# Power_Switch.net
KiCad netlist of a schematic drawn in EasyEDA Pro
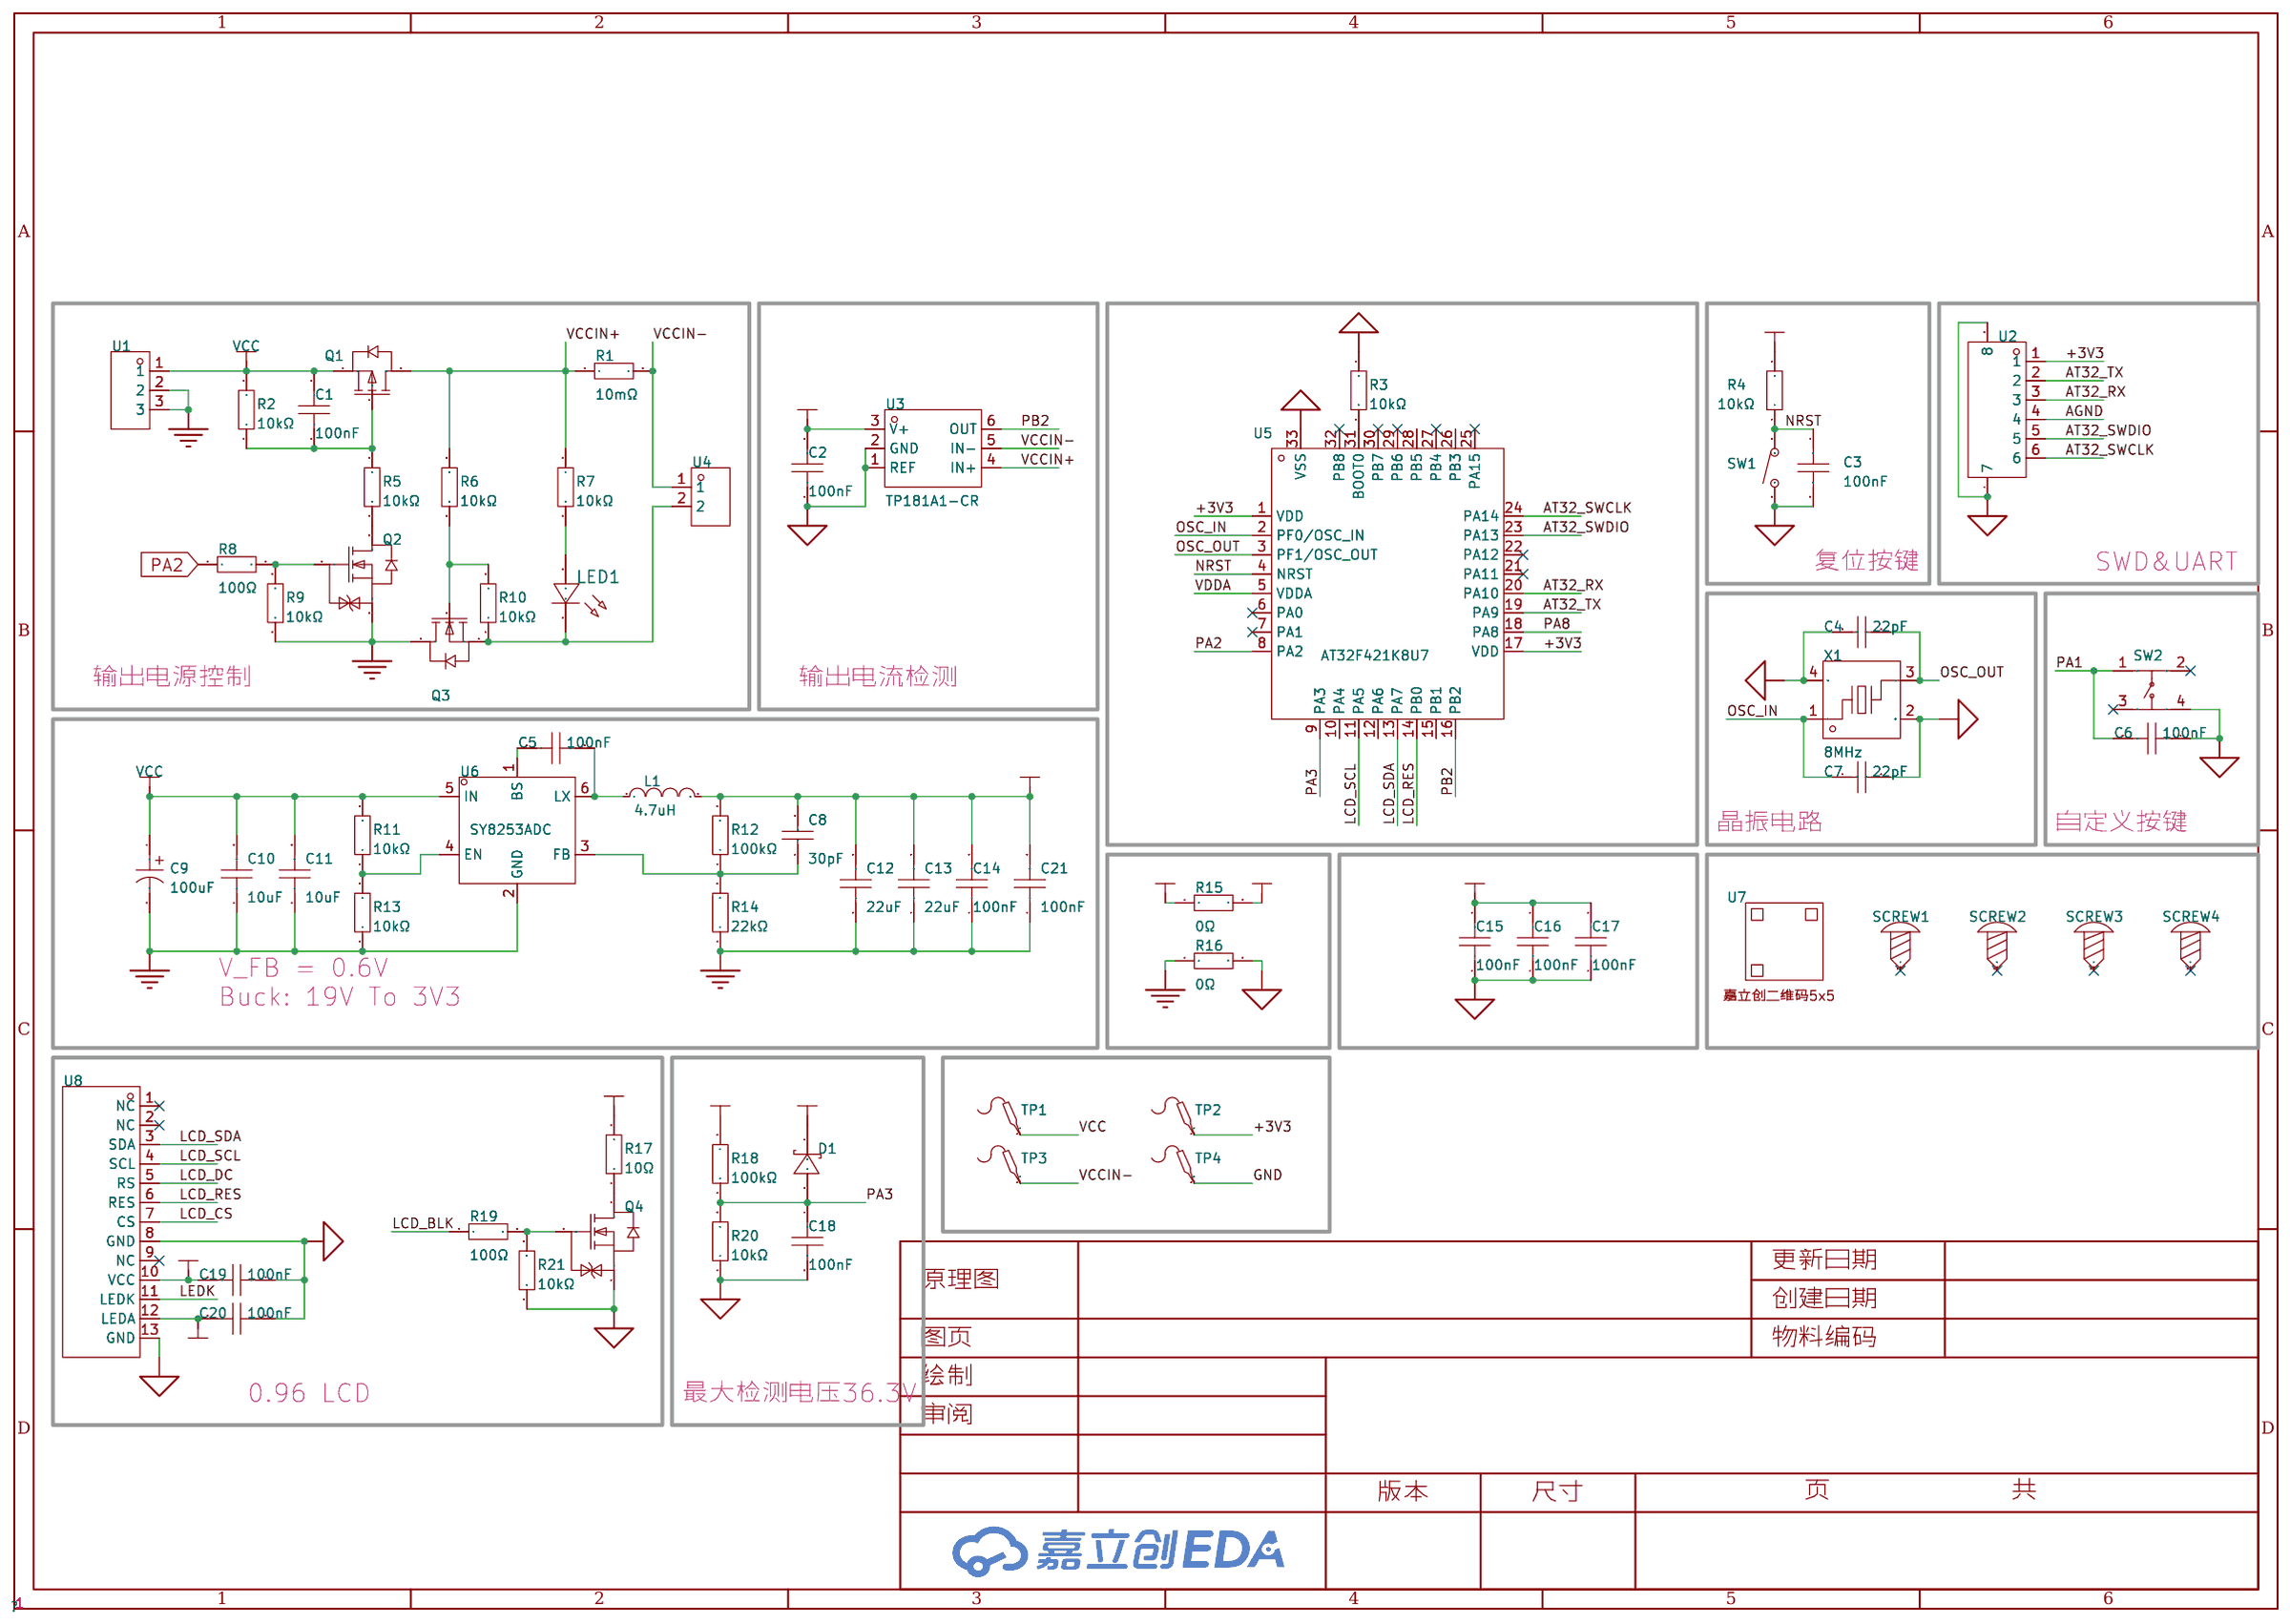
[diagram p0: schematic sheet]

(export (version "E")
  (design (tool "Eeschema 10.0.6"))
  (components
    (comp (ref "C1")
      (value "100nF")
      (footprint "easyedapro:C0402")
      (description "容值:100nF;精度:±10%;额定电压:50V;材质(温度系数):X7R;")
      (fields
        (field (name "Manufacturer Part") "CL05B104KB54PNC")
        (field (name "Manufacturer") "SAMSUNG(三星)")
      )
      (libsource (lib "easyedapro") (part "CL05B104KB54PNC"))
    )
    (comp (ref "C2")
      (value "100nF")
      (footprint "easyedapro:C0402")
      (description "容值:100nF;精度:±10%;额定电压:50V;材质(温度系数):X7R;")
      (fields
        (field (name "Manufacturer Part") "CL05B104KB54PNC")
        (field (name "Manufacturer") "SAMSUNG(三星)")
      )
      (libsource (lib "easyedapro") (part "CL05B104KB54PNC"))
    )
    (comp (ref "C3")
      (value "100nF")
      (footprint "easyedapro:C0402")
      (description "容值:100nF;精度:±10%;额定电压:50V;材质(温度系数):X7R;")
      (fields
        (field (name "Manufacturer Part") "CL05B104KB54PNC")
        (field (name "Manufacturer") "SAMSUNG(三星)")
      )
      (libsource (lib "easyedapro") (part "CL05B104KB54PNC"))
    )
    (comp (ref "C4")
      (value "22pF")
      (footprint "easyedapro:C0402")
      (description "容值:22pF;精度:±5%;额定电压:50V;材质(温度系数):C0G;")
      (fields (field (name "Manufacturer Part") "0402CG220J500NT") (field (name "Manufacturer") "FH(风华)"))
      (libsource (lib "easyedapro") (part "0402CG220J500NT"))
    )
    (comp (ref "C5")
      (value "100nF")
      (footprint "easyedapro:C0402")
      (description "容值:100nF;精度:±10%;额定电压:50V;材质(温度系数):X7R;")
      (fields
        (field (name "Manufacturer Part") "CL05B104KB54PNC")
        (field (name "Manufacturer") "SAMSUNG(三星)")
      )
      (libsource (lib "easyedapro") (part "CL05B104KB54PNC"))
    )
    (comp (ref "C6")
      (value "100nF")
      (footprint "easyedapro:C0402")
      (description "容值:100nF;精度:±10%;额定电压:50V;材质(温度系数):X7R;")
      (fields
        (field (name "Manufacturer Part") "CL05B104KB54PNC")
        (field (name "Manufacturer") "SAMSUNG(三星)")
      )
      (libsource (lib "easyedapro") (part "CL05B104KB54PNC"))
    )
    (comp (ref "C7")
      (value "22pF")
      (footprint "easyedapro:C0402")
      (description "容值:22pF;精度:±5%;额定电压:50V;材质(温度系数):C0G;")
      (fields (field (name "Manufacturer Part") "0402CG220J500NT") (field (name "Manufacturer") "FH(风华)"))
      (libsource (lib "easyedapro") (part "0402CG220J500NT"))
    )
    (comp (ref "C8")
      (value "30pF")
      (footprint "easyedapro:C0402")
      (description "容值:30pF;精度:±5%;额定电压:50V;材质(温度系数):NP0;")
      (fields
        (field (name "Manufacturer Part") "CC0402JRNPO9BN300")
        (field (name "Manufacturer") "YAGEO(国巨)")
      )
      (libsource (lib "easyedapro") (part "CC0402JRNPO9BN300"))
    )
    (comp (ref "C9")
      (value "100uF")
      (footprint "easyedapro:CAP-SMD_BD6.3-L6.6-W6.6-LS7.4-FD")
      (description "容值:100uF;精度:±20%;额定电压:35V;纹波电流:87mA@120kHz;等效串联电阻:-;")
      (fields
        (field (name "Manufacturer Part") "RVT100UF35V67RV0034")
        (field (name "Manufacturer") "KNSCHA(科尼盛)")
      )
      (libsource (lib "easyedapro") (part "RVT100UF35V67RV0034"))
    )
    (comp (ref "C10")
      (value "10uF")
      (footprint "easyedapro:C0805")
      (description "容值:10uF;精度:±10%;额定电压:25V;材质(温度系数):X5R;")
      (fields
        (field (name "Manufacturer Part") "CL21A106KAYNNNE")
        (field (name "Manufacturer") "SAMSUNG(三星)")
      )
      (libsource (lib "easyedapro") (part "CL21A106KAYNNNE"))
    )
    (comp (ref "C11")
      (value "10uF")
      (footprint "easyedapro:C0805")
      (description "容值:10uF;精度:±10%;额定电压:25V;材质(温度系数):X5R;")
      (fields
        (field (name "Manufacturer Part") "CL21A106KAYNNNE")
        (field (name "Manufacturer") "SAMSUNG(三星)")
      )
      (libsource (lib "easyedapro") (part "CL21A106KAYNNNE"))
    )
    (comp (ref "C12")
      (value "22uF")
      (footprint "easyedapro:C0603")
      (description "容值:22uF;精度:±20%;额定电压:6.3V;材质(温度系数):X5R;")
      (fields
        (field (name "Manufacturer Part") "CL10A226MQ8NRNC")
        (field (name "Manufacturer") "SAMSUNG(三星)")
      )
      (libsource (lib "easyedapro") (part "CL10A226MQ8NRNC"))
    )
    (comp (ref "C13")
      (value "22uF")
      (footprint "easyedapro:C0603")
      (description "容值:22uF;精度:±20%;额定电压:6.3V;材质(温度系数):X5R;")
      (fields
        (field (name "Manufacturer Part") "CL10A226MQ8NRNC")
        (field (name "Manufacturer") "SAMSUNG(三星)")
      )
      (libsource (lib "easyedapro") (part "CL10A226MQ8NRNC"))
    )
    (comp (ref "C14")
      (value "100nF")
      (footprint "easyedapro:C0402")
      (description "容值:100nF;精度:±10%;额定电压:50V;材质(温度系数):X7R;")
      (fields
        (field (name "Manufacturer Part") "CL05B104KB54PNC")
        (field (name "Manufacturer") "SAMSUNG(三星)")
      )
      (libsource (lib "easyedapro") (part "CL05B104KB54PNC"))
    )
    (comp (ref "C15")
      (value "100nF")
      (footprint "easyedapro:C0402")
      (description "容值:100nF;精度:±10%;额定电压:50V;材质(温度系数):X7R;")
      (fields
        (field (name "Manufacturer Part") "CL05B104KB54PNC")
        (field (name "Manufacturer") "SAMSUNG(三星)")
      )
      (libsource (lib "easyedapro") (part "CL05B104KB54PNC"))
    )
    (comp (ref "C16")
      (value "100nF")
      (footprint "easyedapro:C0402")
      (description "容值:100nF;精度:±10%;额定电压:50V;材质(温度系数):X7R;")
      (fields
        (field (name "Manufacturer Part") "CL05B104KB54PNC")
        (field (name "Manufacturer") "SAMSUNG(三星)")
      )
      (libsource (lib "easyedapro") (part "CL05B104KB54PNC"))
    )
    (comp (ref "C17")
      (value "100nF")
      (footprint "easyedapro:C0402")
      (description "容值:100nF;精度:±10%;额定电压:50V;材质(温度系数):X7R;")
      (fields
        (field (name "Manufacturer Part") "CL05B104KB54PNC")
        (field (name "Manufacturer") "SAMSUNG(三星)")
      )
      (libsource (lib "easyedapro") (part "CL05B104KB54PNC"))
    )
    (comp (ref "C18")
      (value "100nF")
      (footprint "easyedapro:C0402")
      (description "容值:100nF;精度:±10%;额定电压:50V;材质(温度系数):X7R;")
      (fields
        (field (name "Manufacturer Part") "CL05B104KB54PNC")
        (field (name "Manufacturer") "SAMSUNG(三星)")
      )
      (libsource (lib "easyedapro") (part "CL05B104KB54PNC"))
    )
    (comp (ref "C19")
      (value "100nF")
      (footprint "easyedapro:C0402")
      (description "容值:100nF;精度:±10%;额定电压:50V;材质(温度系数):X7R;")
      (fields
        (field (name "Manufacturer Part") "CL05B104KB54PNC")
        (field (name "Manufacturer") "SAMSUNG(三星)")
      )
      (libsource (lib "easyedapro") (part "CL05B104KB54PNC"))
    )
    (comp (ref "C20")
      (value "100nF")
      (footprint "easyedapro:C0402")
      (description "容值:100nF;精度:±10%;额定电压:50V;材质(温度系数):X7R;")
      (fields
        (field (name "Manufacturer Part") "CL05B104KB54PNC")
        (field (name "Manufacturer") "SAMSUNG(三星)")
      )
      (libsource (lib "easyedapro") (part "CL05B104KB54PNC"))
    )
    (comp (ref "C21")
      (value "100nF")
      (footprint "easyedapro:C0402")
      (description "容值:100nF;精度:±10%;额定电压:50V;材质(温度系数):X7R;")
      (fields
        (field (name "Manufacturer Part") "CL05B104KB54PNC")
        (field (name "Manufacturer") "SAMSUNG(三星)")
      )
      (libsource (lib "easyedapro") (part "CL05B104KB54PNC"))
    )
    (comp (ref "D1")
      (value "SD103AWS")
      (footprint "easyedapro:SOD-323_L1.8-W1.3-LS2.5-RD")
      (description "正向压降(Vf):600mV@200mA;直流反向耐压(Vr):40V;平均整流电流(Io):350mA;")
      (fields (field (name "Manufacturer") "Hottech(合科泰)"))
      (libsource (lib "easyedapro") (part "SD103AWS_C181207"))
    )
    (comp (ref "L1")
      (value "4.7uH")
      (footprint "easyedapro:IND-SMD_L5.4-W5.2_FXL0530")
      (description "电感值:4.7uH;精度:±20%;额定电流:4.5A;饱和电流(Isat):5A;类型:一体成型电感;")
      (fields (field (name "Manufacturer Part") "FXL0530-4R7-M") (field (name "Manufacturer") "cjiang(长江微电)"))
      (libsource (lib "easyedapro") (part "FXL0530-4R7-M"))
    )
    (comp (ref "LED1")
      (value "~")
      (footprint "easyedapro:LED_0603")
      (libsource (lib "easyedapro") (part "LED_R"))
    )
    (comp (ref "Q1")
      (value "NCE30P25S")
      (footprint "easyedapro:SOIC-8_L5.0-W4.0-P1.27-LS6.0-BL")
      (fields (field (name "Manufacturer") "NCE(无锡新洁能)"))
      (libsource (lib "easyedapro") (part "NCE30P25S"))
    )
    (comp (ref "Q2")
      (value "BR2N7002K2")
      (footprint "easyedapro:SOT-23-3_L2.9-W1.6-P1.90-LS2.8-BR")
      (fields (field (name "Manufacturer") "BLUE ROCKET(蓝箭)"))
      (libsource (lib "easyedapro") (part "BR2N7002K2"))
    )
    (comp (ref "Q3")
      (value "NCEP4045GU")
      (footprint "easyedapro:DFN-8_L5.8-W4.9-P1.27-LS6.0-BL-1")
      (fields (field (name "Manufacturer") "NCE(无锡新洁能)"))
      (libsource (lib "easyedapro") (part "NCEP4045GU"))
    )
    (comp (ref "Q4")
      (value "BR2N7002K2")
      (footprint "easyedapro:SOT-23-3_L2.9-W1.6-P1.90-LS2.8-BR")
      (fields (field (name "Manufacturer") "BLUE ROCKET(蓝箭)"))
      (libsource (lib "easyedapro") (part "BR2N7002K2"))
    )
    (comp (ref "R1")
      (value "10mΩ")
      (footprint "easyedapro:R2512")
      (description "阻值:10mΩ;精度:±1%;功率:2W;温度系数:±70ppm/°C;")
      (fields (field (name "Manufacturer Part") "FMF25FPJR010-LH") (field (name "Manufacturer") "PSA(信昌电陶)"))
      (libsource (lib "easyedapro") (part "FMF25FPJR010-LHL"))
    )
    (comp (ref "R2")
      (value "10kΩ")
      (footprint "easyedapro:R0402")
      (description "电阻类型:厚膜电阻;阻值:10kΩ;精度:±1%;功率:62.5mW;最大工作电压:50V;温度系数:±100ppm/°C;")
      (fields
        (field (name "Manufacturer Part") "0402WGF1002TCE")
        (field (name "Manufacturer") "UNI-ROYAL(厚声)")
      )
      (libsource (lib "easyedapro") (part "0402WGF1002TCE"))
    )
    (comp (ref "R3")
      (value "10kΩ")
      (footprint "easyedapro:R0402")
      (description "电阻类型:厚膜电阻;阻值:10kΩ;精度:±1%;功率:62.5mW;最大工作电压:50V;温度系数:±100ppm/°C;")
      (fields
        (field (name "Manufacturer Part") "0402WGF1002TCE")
        (field (name "Manufacturer") "UNI-ROYAL(厚声)")
      )
      (libsource (lib "easyedapro") (part "0402WGF1002TCE"))
    )
    (comp (ref "R4")
      (value "10kΩ")
      (footprint "easyedapro:R0402")
      (description "电阻类型:厚膜电阻;阻值:10kΩ;精度:±1%;功率:62.5mW;最大工作电压:50V;温度系数:±100ppm/°C;")
      (fields
        (field (name "Manufacturer Part") "0402WGF1002TCE")
        (field (name "Manufacturer") "UNI-ROYAL(厚声)")
      )
      (libsource (lib "easyedapro") (part "0402WGF1002TCE"))
    )
    (comp (ref "R5")
      (value "10kΩ")
      (footprint "easyedapro:R0402")
      (description "电阻类型:厚膜电阻;阻值:10kΩ;精度:±1%;功率:62.5mW;最大工作电压:50V;温度系数:±100ppm/°C;")
      (fields
        (field (name "Manufacturer Part") "0402WGF1002TCE")
        (field (name "Manufacturer") "UNI-ROYAL(厚声)")
      )
      (libsource (lib "easyedapro") (part "0402WGF1002TCE"))
    )
    (comp (ref "R6")
      (value "10kΩ")
      (footprint "easyedapro:R0402")
      (description "电阻类型:厚膜电阻;阻值:10kΩ;精度:±1%;功率:62.5mW;最大工作电压:50V;温度系数:±100ppm/°C;")
      (fields
        (field (name "Manufacturer Part") "0402WGF1002TCE")
        (field (name "Manufacturer") "UNI-ROYAL(厚声)")
      )
      (libsource (lib "easyedapro") (part "0402WGF1002TCE"))
    )
    (comp (ref "R7")
      (value "10kΩ")
      (footprint "easyedapro:R0402")
      (description "电阻类型:厚膜电阻;阻值:10kΩ;精度:±1%;功率:62.5mW;最大工作电压:50V;温度系数:±100ppm/°C;")
      (fields
        (field (name "Manufacturer Part") "0402WGF1002TCE")
        (field (name "Manufacturer") "UNI-ROYAL(厚声)")
      )
      (libsource (lib "easyedapro") (part "0402WGF1002TCE"))
    )
    (comp (ref "R8")
      (value "100Ω")
      (footprint "easyedapro:R0402")
      (description "电阻类型:厚膜电阻;阻值:100Ω;精度:±1%;功率:62.5mW;最大工作电压:50V;温度系数:±200ppm/°C;")
      (fields
        (field (name "Manufacturer Part") "0402WGF1000TCE")
        (field (name "Manufacturer") "UNI-ROYAL(厚声)")
      )
      (libsource (lib "easyedapro") (part "0402WGF1000TCE"))
    )
    (comp (ref "R9")
      (value "10kΩ")
      (footprint "easyedapro:R0402")
      (description "电阻类型:厚膜电阻;阻值:10kΩ;精度:±1%;功率:62.5mW;最大工作电压:50V;温度系数:±100ppm/°C;")
      (fields
        (field (name "Manufacturer Part") "0402WGF1002TCE")
        (field (name "Manufacturer") "UNI-ROYAL(厚声)")
      )
      (libsource (lib "easyedapro") (part "0402WGF1002TCE"))
    )
    (comp (ref "R10")
      (value "10kΩ")
      (footprint "easyedapro:R0402")
      (description "电阻类型:厚膜电阻;阻值:10kΩ;精度:±1%;功率:62.5mW;最大工作电压:50V;温度系数:±100ppm/°C;")
      (fields
        (field (name "Manufacturer Part") "0402WGF1002TCE")
        (field (name "Manufacturer") "UNI-ROYAL(厚声)")
      )
      (libsource (lib "easyedapro") (part "0402WGF1002TCE"))
    )
    (comp (ref "R11")
      (value "10kΩ")
      (footprint "easyedapro:R0402")
      (description "电阻类型:厚膜电阻;阻值:10kΩ;精度:±1%;功率:62.5mW;最大工作电压:50V;温度系数:±100ppm/°C;")
      (fields
        (field (name "Manufacturer Part") "0402WGF1002TCE")
        (field (name "Manufacturer") "UNI-ROYAL(厚声)")
      )
      (libsource (lib "easyedapro") (part "0402WGF1002TCE"))
    )
    (comp (ref "R12")
      (value "100kΩ")
      (footprint "easyedapro:R0402")
      (description "电阻类型:厚膜电阻;阻值:100kΩ;精度:±1%;功率:62.5mW;最大工作电压:50V;温度系数:±100ppm/°C;")
      (fields
        (field (name "Manufacturer Part") "0402WGF1003TCE")
        (field (name "Manufacturer") "UNI-ROYAL(厚声)")
      )
      (libsource (lib "easyedapro") (part "0402WGF1003TCE"))
    )
    (comp (ref "R13")
      (value "10kΩ")
      (footprint "easyedapro:R0402")
      (description "电阻类型:厚膜电阻;阻值:10kΩ;精度:±1%;功率:62.5mW;最大工作电压:50V;温度系数:±100ppm/°C;")
      (fields
        (field (name "Manufacturer Part") "0402WGF1002TCE")
        (field (name "Manufacturer") "UNI-ROYAL(厚声)")
      )
      (libsource (lib "easyedapro") (part "0402WGF1002TCE"))
    )
    (comp (ref "R14")
      (value "22kΩ")
      (footprint "easyedapro:R0402")
      (description "电阻类型:厚膜电阻;阻值:22kΩ;精度:±1%;功率:62.5mW;最大工作电压:50V;温度系数:±100ppm/°C;")
      (fields
        (field (name "Manufacturer Part") "0402WGF2202TCE")
        (field (name "Manufacturer") "UNI-ROYAL(厚声)")
      )
      (libsource (lib "easyedapro") (part "0402WGF2202TCE"))
    )
    (comp (ref "R15")
      (value "0Ω")
      (footprint "easyedapro:R0402")
      (description "电阻类型:厚膜电阻;阻值:0Ω;精度:±1%;功率:62.5mW;最大工作电压:50V;温度系数:±800ppm/°C;")
      (fields
        (field (name "Manufacturer Part") "0402WGF0000TCE")
        (field (name "Manufacturer") "UNI-ROYAL(厚声)")
      )
      (libsource (lib "easyedapro") (part "0402WGF0000TCE"))
    )
    (comp (ref "R16")
      (value "0Ω")
      (footprint "easyedapro:R0402")
      (description "电阻类型:厚膜电阻;阻值:0Ω;精度:±1%;功率:62.5mW;最大工作电压:50V;温度系数:±800ppm/°C;")
      (fields
        (field (name "Manufacturer Part") "0402WGF0000TCE")
        (field (name "Manufacturer") "UNI-ROYAL(厚声)")
      )
      (libsource (lib "easyedapro") (part "0402WGF0000TCE"))
    )
    (comp (ref "R17")
      (value "10Ω")
      (footprint "easyedapro:R0402")
      (description "电阻类型:厚膜电阻;阻值:10Ω;精度:±1%;功率:62.5mW;最大工作电压:50V;温度系数:±200ppm/°C;")
      (fields
        (field (name "Manufacturer Part") "0402WGF100JTCE")
        (field (name "Manufacturer") "UNI-ROYAL(厚声)")
      )
      (libsource (lib "easyedapro") (part "0402WGF100JTCE"))
    )
    (comp (ref "R18")
      (value "100kΩ")
      (footprint "easyedapro:R0402")
      (description "电阻类型:厚膜电阻;阻值:100kΩ;精度:±1%;功率:62.5mW;最大工作电压:50V;温度系数:±100ppm/°C;")
      (fields
        (field (name "Manufacturer Part") "0402WGF1003TCE")
        (field (name "Manufacturer") "UNI-ROYAL(厚声)")
      )
      (libsource (lib "easyedapro") (part "0402WGF1003TCE"))
    )
    (comp (ref "R19")
      (value "100Ω")
      (footprint "easyedapro:R0402")
      (description "电阻类型:厚膜电阻;阻值:100Ω;精度:±1%;功率:62.5mW;最大工作电压:50V;温度系数:±200ppm/°C;")
      (fields
        (field (name "Manufacturer Part") "0402WGF1000TCE")
        (field (name "Manufacturer") "UNI-ROYAL(厚声)")
      )
      (libsource (lib "easyedapro") (part "0402WGF1000TCE"))
    )
    (comp (ref "R20")
      (value "10kΩ")
      (footprint "easyedapro:R0402")
      (description "电阻类型:厚膜电阻;阻值:10kΩ;精度:±1%;功率:62.5mW;最大工作电压:50V;温度系数:±100ppm/°C;")
      (fields
        (field (name "Manufacturer Part") "0402WGF1002TCE")
        (field (name "Manufacturer") "UNI-ROYAL(厚声)")
      )
      (libsource (lib "easyedapro") (part "0402WGF1002TCE"))
    )
    (comp (ref "R21")
      (value "10kΩ")
      (footprint "easyedapro:R0402")
      (description "电阻类型:厚膜电阻;阻值:10kΩ;精度:±1%;功率:62.5mW;最大工作电压:50V;温度系数:±100ppm/°C;")
      (fields
        (field (name "Manufacturer Part") "0402WGF1002TCE")
        (field (name "Manufacturer") "UNI-ROYAL(厚声)")
      )
      (libsource (lib "easyedapro") (part "0402WGF1002TCE"))
    )
    (comp (ref "SCREW1")
      (value "~")
      (footprint "easyedapro:M2螺丝")
      (libsource (lib "easyedapro") (part "螺丝孔"))
    )
    (comp (ref "SCREW2")
      (value "~")
      (footprint "easyedapro:M2螺丝")
      (libsource (lib "easyedapro") (part "螺丝孔"))
    )
    (comp (ref "SCREW3")
      (value "~")
      (footprint "easyedapro:M2螺丝")
      (libsource (lib "easyedapro") (part "螺丝孔"))
    )
    (comp (ref "SCREW4")
      (value "~")
      (footprint "easyedapro:M2螺丝")
      (libsource (lib "easyedapro") (part "螺丝孔"))
    )
    (comp (ref "SW1")
      (value "TS-1185-B-A-B-A")
      (footprint "easyedapro:SW-SMD_L4.0-W3.0-LS5.0")
      (fields (field (name "Manufacturer") "XKB Connectivity(中国星坤)"))
      (libsource (lib "easyedapro") (part "TS-1185-B-A-B-A"))
    )
    (comp (ref "SW2")
      (value "TS-1102S-B-C-B")
      (footprint "easyedapro:KEY-SMD_4P-L6.0-W6.0-P4.50-LS8.6")
      (fields (field (name "Manufacturer") "XKB Connectivity(中国星坤)"))
      (libsource (lib "easyedapro") (part "TS-1102S-B-C-B"))
    )
    (comp (ref "TP1")
      (value "~")
      (footprint "easyedapro:Test-Point-0.5mm")
      (description "Test Point 测试点")
      (libsource (lib "easyedapro") (part "Test-Point"))
    )
    (comp (ref "TP2")
      (value "~")
      (footprint "easyedapro:Test-Point-0.5mm")
      (description "Test Point 测试点")
      (libsource (lib "easyedapro") (part "Test-Point"))
    )
    (comp (ref "TP3")
      (value "~")
      (footprint "easyedapro:Test-Point-0.5mm")
      (description "Test Point 测试点")
      (libsource (lib "easyedapro") (part "Test-Point"))
    )
    (comp (ref "TP4")
      (value "~")
      (footprint "easyedapro:Test-Point-0.5mm")
      (description "Test Point 测试点")
      (libsource (lib "easyedapro") (part "Test-Point"))
    )
    (comp (ref "U1")
      (value "HC-DC-007B-2.5")
      (footprint "easyedapro:DC-IN-TH_HC-DC-007B-2.5")
      (description "连接器类型:DC电源插座;安装方式:弯插;触点内径:2.5mm;触点外径:6.45mm;额定电流:8A;额定电压:24V;触头材质:黄铜;触头镀层:锡;工作温度范围:-30°C~+70°C;")
      (fields (field (name "Manufacturer") "HCTL(华灿天禄)"))
      (libsource (lib "easyedapro") (part "HC-DC-007B-2.5"))
    )
    (comp (ref "U2")
      (value "WAFER-GH1.25-6PWB")
      (footprint "easyedapro:CONN-SMD_6P-P1.25_XUNPU_WAFER-GH1.25-6PWB")
      (description "插针结构:1x6P;间距:1.25mm;安装方式:卧贴;参考系列:GH;总PIN数:6P;排数:1;每排PIN数:6;额定电流:1A;工作温度范围:-25°C~+85°C;")
      (fields (field (name "Manufacturer") "XUNPU(讯普)"))
      (libsource (lib "easyedapro") (part "WAFER-GH1.25-6PWB"))
    )
    (comp (ref "U3")
      (value "TP181A1-CR")
      (footprint "easyedapro:SC70-6_L2.1-W1.3-P0.65-LS2.3-BL")
      (fields (field (name "Manufacturer") "3PEAK"))
      (libsource (lib "easyedapro") (part "TP181A1-CR"))
    )
    (comp (ref "U4")
      (value "KF301-5.0-2P")
      (footprint "easyedapro:CONN-TH_P5.00_KF301-5.0-2P")
      (fields (field (name "Manufacturer") "KEFA(科发)"))
      (libsource (lib "easyedapro") (part "KF301-5.0-2P"))
    )
    (comp (ref "U5")
      (value "AT32F421K8U7")
      (footprint "easyedapro:QFN-32_L5.0-W5.0-P0.50-BL-EP3.4")
      (fields (field (name "Manufacturer") "ARTERY(雅特力)"))
      (libsource (lib "easyedapro") (part "AT32F421K8U7"))
    )
    (comp (ref "U6")
      (value "SY8253ADC")
      (footprint "easyedapro:SOT-23-6_L2.9-W1.6-P0.95-LS2.8-BR")
      (description "功能类型:降压型;输入电压:-;输出电流(最大值):-;")
      (fields (field (name "Manufacturer") "silergy(矽力杰)"))
      (libsource (lib "easyedapro") (part "SY8253ADC"))
    )
    (comp (ref "U7")
      (value "~")
      (footprint "easyedapro:JLC-QRCODE-5x5")
      (libsource (lib "easyedapro") (part "嘉立创二维码5x5"))
    )
    (comp (ref "U8")
      (value "HS096T01H13")
      (footprint "easyedapro:LCD-SMD_HS096T01H13")
      (description "主控芯片:ST7735;尺寸(inch):0.96;")
      (fields (field (name "Manufacturer") "HS(汉昇)"))
      (libsource (lib "easyedapro") (part "HS096T01H13"))
    )
    (comp (ref "X1")
      (value "8MHz")
      (footprint "easyedapro:OSC-SMD_4P-L3.2-W2.5-BL")
      (description "晶振类型:贴片晶振;频率:8MHz;常温频差:±10ppm;外接负载电容:12pF;频率稳定度(全温):±20ppm;")
      (fields (field (name "Manufacturer Part") "X32258MOB4SI") (field (name "Manufacturer") "YXC(扬兴晶振)"))
      (libsource (lib "easyedapro") (part "X32258MOB4SI"))
    )
  )
  (nets
    (net (code "1") (name "+3V3") (class "Default")
      (node (ref "C12") (pin "2") (pinfunction "2_2") (pintype "unspecified"))
      (node (ref "C13") (pin "2") (pinfunction "2_2") (pintype "unspecified"))
      (node (ref "C14") (pin "2") (pinfunction "2_2") (pintype "input"))
      (node (ref "C15") (pin "2") (pinfunction "2_2") (pintype "input"))
      (node (ref "C16") (pin "2") (pinfunction "2_2") (pintype "input"))
      (node (ref "C17") (pin "2") (pinfunction "2_2") (pintype "input"))
      (node (ref "C19") (pin "2") (pinfunction "2_2") (pintype "input"))
      (node (ref "C2") (pin "2") (pinfunction "2_2") (pintype "input"))
      (node (ref "C20") (pin "2") (pinfunction "2_2") (pintype "input"))
      (node (ref "C21") (pin "2") (pinfunction "2_2") (pintype "input"))
      (node (ref "C8") (pin "2") (pinfunction "2_2") (pintype "input"))
      (node (ref "D1") (pin "1") (pinfunction "C_1") (pintype "unspecified"))
      (node (ref "L1") (pin "2") (pinfunction "2_2") (pintype "unspecified"))
      (node (ref "R12") (pin "2") (pinfunction "2_2") (pintype "input"))
      (node (ref "R15") (pin "1") (pinfunction "1_1") (pintype "input"))
      (node (ref "R4") (pin "2") (pinfunction "2_2") (pintype "input"))
      (node (ref "TP2") (pin "1") (pinfunction "1_1") (pintype "input"))
      (node (ref "U2") (pin "1") (pinfunction "1_1") (pintype "unspecified"))
      (node (ref "U3") (pin "3") (pinfunction "V+_3") (pintype "unspecified"))
      (node (ref "U5") (pin "1") (pinfunction "VDD_1") (pintype "unspecified"))
      (node (ref "U5") (pin "17") (pinfunction "VDD_17") (pintype "unspecified"))
      (node (ref "U8") (pin "10") (pinfunction "VCC_10") (pintype "unspecified"))
      (node (ref "U8") (pin "12") (pinfunction "LEDA_12") (pintype "unspecified"))
    )
    (net (code "2") (name "/AT32_RX") (class "Default")
      (node (ref "U2") (pin "3") (pinfunction "3_3") (pintype "unspecified"))
      (node (ref "U5") (pin "20") (pinfunction "PA10_20") (pintype "unspecified"))
    )
    (net (code "3") (name "/AT32_SWCLK") (class "Default")
      (node (ref "U2") (pin "6") (pinfunction "6_6") (pintype "unspecified"))
      (node (ref "U5") (pin "24") (pinfunction "PA14_24") (pintype "unspecified"))
    )
    (net (code "4") (name "/AT32_SWDIO") (class "Default")
      (node (ref "U2") (pin "5") (pinfunction "5_5") (pintype "unspecified"))
      (node (ref "U5") (pin "23") (pinfunction "PA13_23") (pintype "unspecified"))
    )
    (net (code "5") (name "/AT32_TX") (class "Default")
      (node (ref "U2") (pin "2") (pinfunction "2_2") (pintype "unspecified"))
      (node (ref "U5") (pin "19") (pinfunction "PA9_19") (pintype "unspecified"))
    )
    (net (code "6") (name "/LCD_BLK") (class "Default")
      (node (ref "R19") (pin "1") (pinfunction "1_1") (pintype "input"))
    )
    (net (code "7") (name "/LCD_CS") (class "Default")
      (node (ref "U8") (pin "7") (pinfunction "CS_7") (pintype "unspecified"))
    )
    (net (code "8") (name "/LCD_DC") (class "Default")
      (node (ref "U8") (pin "5") (pinfunction "RS_5") (pintype "unspecified"))
    )
    (net (code "9") (name "/LCD_RES") (class "Default")
      (node (ref "U5") (pin "14") (pinfunction "PB0_14") (pintype "unspecified"))
      (node (ref "U8") (pin "6") (pinfunction "RES_6") (pintype "unspecified"))
    )
    (net (code "10") (name "/LCD_SCL") (class "Default")
      (node (ref "U5") (pin "11") (pinfunction "PA5_11") (pintype "unspecified"))
      (node (ref "U8") (pin "4") (pinfunction "SCL_4") (pintype "unspecified"))
    )
    (net (code "11") (name "/LCD_SDA") (class "Default")
      (node (ref "U5") (pin "13") (pinfunction "PA7_13") (pintype "unspecified"))
      (node (ref "U8") (pin "3") (pinfunction "SDA_3") (pintype "unspecified"))
    )
    (net (code "12") (name "/NRST") (class "Default")
      (node (ref "C3") (pin "1") (pinfunction "1_1") (pintype "input"))
      (node (ref "R4") (pin "1") (pinfunction "1_1") (pintype "input"))
      (node (ref "SW1") (pin "1") (pinfunction "1_1") (pintype "input"))
      (node (ref "U5") (pin "4") (pinfunction "NRST_4") (pintype "unspecified"))
    )
    (net (code "13") (name "/OSC_IN") (class "Default")
      (node (ref "C7") (pin "1") (pinfunction "1_1") (pintype "input"))
      (node (ref "U5") (pin "2") (pinfunction "PF0/OSC_IN_2") (pintype "unspecified"))
      (node (ref "X1") (pin "1") (pinfunction "1_1") (pintype "input"))
    )
    (net (code "14") (name "/OSC_OUT") (class "Default")
      (node (ref "C4") (pin "2") (pinfunction "2_2") (pintype "input"))
      (node (ref "U5") (pin "3") (pinfunction "PF1/OSC_OUT_3") (pintype "unspecified"))
      (node (ref "X1") (pin "3") (pinfunction "3_3") (pintype "input"))
    )
    (net (code "15") (name "/PA1") (class "Default")
      (node (ref "C6") (pin "2") (pinfunction "2_2") (pintype "input"))
      (node (ref "SW2") (pin "1") (pinfunction "1_1") (pintype "input"))
    )
    (net (code "16") (name "/PA3") (class "Default")
      (node (ref "C18") (pin "1") (pinfunction "1_1") (pintype "input"))
      (node (ref "D1") (pin "2") (pinfunction "A_2") (pintype "unspecified"))
      (node (ref "R18") (pin "1") (pinfunction "1_1") (pintype "input"))
      (node (ref "R20") (pin "2") (pinfunction "2_2") (pintype "input"))
      (node (ref "U5") (pin "9") (pinfunction "PA3_9") (pintype "unspecified"))
    )
    (net (code "17") (name "/PA8") (class "Default")
      (node (ref "U5") (pin "18") (pinfunction "PA8_18") (pintype "unspecified"))
    )
    (net (code "18") (name "/PB2") (class "Default")
      (node (ref "U3") (pin "6") (pinfunction "OUT_6") (pintype "unspecified"))
      (node (ref "U5") (pin "16") (pinfunction "PB2_16") (pintype "unspecified"))
    )
    (net (code "19") (name "/VCCIN+") (class "Default")
      (node (ref "Q1") (pin "2") (pinfunction "D_2") (pintype "input"))
      (node (ref "R1") (pin "1") (pinfunction "1_1") (pintype "input"))
      (node (ref "R6") (pin "2") (pinfunction "2_2") (pintype "input"))
      (node (ref "R7") (pin "2") (pinfunction "2_2") (pintype "input"))
      (node (ref "U3") (pin "4") (pinfunction "IN+_4") (pintype "unspecified"))
    )
    (net (code "20") (name "AGND") (class "Default")
      (node (ref "C15") (pin "1") (pinfunction "1_1") (pintype "input"))
      (node (ref "C16") (pin "1") (pinfunction "1_1") (pintype "input"))
      (node (ref "C17") (pin "1") (pinfunction "1_1") (pintype "input"))
      (node (ref "C18") (pin "2") (pinfunction "2_2") (pintype "input"))
      (node (ref "C19") (pin "1") (pinfunction "1_1") (pintype "input"))
      (node (ref "C2") (pin "1") (pinfunction "1_1") (pintype "input"))
      (node (ref "C20") (pin "1") (pinfunction "1_1") (pintype "input"))
      (node (ref "C3") (pin "2") (pinfunction "2_2") (pintype "input"))
      (node (ref "C4") (pin "1") (pinfunction "1_1") (pintype "input"))
      (node (ref "C6") (pin "1") (pinfunction "1_1") (pintype "input"))
      (node (ref "C7") (pin "2") (pinfunction "2_2") (pintype "input"))
      (node (ref "Q4") (pin "2") (pinfunction "S_2") (pintype "unspecified"))
      (node (ref "R16") (pin "2") (pinfunction "2_2") (pintype "input"))
      (node (ref "R20") (pin "1") (pinfunction "1_1") (pintype "input"))
      (node (ref "R21") (pin "1") (pinfunction "1_1") (pintype "input"))
      (node (ref "R3") (pin "1") (pinfunction "1_1") (pintype "input"))
      (node (ref "SW1") (pin "2") (pinfunction "2_2") (pintype "input"))
      (node (ref "SW2") (pin "4") (pinfunction "4_4") (pintype "input"))
      (node (ref "U2") (pin "4") (pinfunction "4_4") (pintype "unspecified"))
      (node (ref "U2") (pin "7") (pinfunction "7_7") (pintype "unspecified"))
      (node (ref "U2") (pin "8") (pinfunction "8_8") (pintype "unspecified"))
      (node (ref "U3") (pin "1") (pinfunction "REF_1") (pintype "unspecified"))
      (node (ref "U3") (pin "2") (pinfunction "GND_2") (pintype "unspecified"))
      (node (ref "U5") (pin "33") (pinfunction "VSS_33") (pintype "unspecified"))
      (node (ref "U8") (pin "13") (pinfunction "GND_13") (pintype "unspecified"))
      (node (ref "U8") (pin "8") (pinfunction "GND_8") (pintype "unspecified"))
      (node (ref "X1") (pin "2") (pinfunction "GND_2") (pintype "input"))
      (node (ref "X1") (pin "4") (pinfunction "GND_4") (pintype "input"))
    )
    (net (code "21") (name "GND") (class "Default")
      (node (ref "C10") (pin "1") (pinfunction "1_1") (pintype "unspecified"))
      (node (ref "C11") (pin "1") (pinfunction "1_1") (pintype "unspecified"))
      (node (ref "C12") (pin "1") (pinfunction "1_1") (pintype "unspecified"))
      (node (ref "C13") (pin "1") (pinfunction "1_1") (pintype "unspecified"))
      (node (ref "C14") (pin "1") (pinfunction "1_1") (pintype "input"))
      (node (ref "C21") (pin "1") (pinfunction "1_1") (pintype "input"))
      (node (ref "C9") (pin "2") (pinfunction "2_2") (pintype "input"))
      (node (ref "Q2") (pin "2") (pinfunction "S_2") (pintype "unspecified"))
      (node (ref "Q3") (pin "3") (pinfunction "D_3") (pintype "input"))
      (node (ref "R13") (pin "1") (pinfunction "1_1") (pintype "input"))
      (node (ref "R14") (pin "1") (pinfunction "1_1") (pintype "input"))
      (node (ref "R16") (pin "1") (pinfunction "1_1") (pintype "input"))
      (node (ref "R9") (pin "1") (pinfunction "1_1") (pintype "input"))
      (node (ref "TP4") (pin "1") (pinfunction "1_1") (pintype "input"))
      (node (ref "U1") (pin "2") (pinfunction "2_2") (pintype "unspecified"))
      (node (ref "U1") (pin "3") (pinfunction "3_3") (pintype "unspecified"))
      (node (ref "U6") (pin "2") (pinfunction "GND_2") (pintype "input"))
    )
    (net (code "22") (name "LEDK") (class "Default")
      (node (ref "R17") (pin "2") (pinfunction "2_2") (pintype "input"))
      (node (ref "U8") (pin "11") (pinfunction "LEDK_11") (pintype "unspecified"))
    )
    (net (code "23") (name "Net-(LED1-A)") (class "Default")
      (node (ref "LED1") (pin "2") (pinfunction "A_2") (pintype "input"))
      (node (ref "R7") (pin "1") (pinfunction "1_1") (pintype "input"))
    )
    (net (code "24") (name "Net-(LED1-C)") (class "Default")
      (node (ref "LED1") (pin "1") (pinfunction "C_1") (pintype "input"))
      (node (ref "Q3") (pin "2") (pinfunction "S_2") (pintype "input"))
      (node (ref "R10") (pin "1") (pinfunction "1_1") (pintype "input"))
      (node (ref "U4") (pin "2") (pinfunction "2_2") (pintype "unspecified"))
    )
    (net (code "25") (name "Net-(Q1-G)") (class "Default")
      (node (ref "C1") (pin "1") (pinfunction "1_1") (pintype "input"))
      (node (ref "Q1") (pin "1") (pinfunction "G_1") (pintype "input"))
      (node (ref "R2") (pin "1") (pinfunction "1_1") (pintype "input"))
      (node (ref "R5") (pin "2") (pinfunction "2_2") (pintype "input"))
    )
    (net (code "26") (name "Net-(Q2-D)") (class "Default")
      (node (ref "Q2") (pin "3") (pinfunction "D_3") (pintype "unspecified"))
      (node (ref "R5") (pin "1") (pinfunction "1_1") (pintype "input"))
    )
    (net (code "27") (name "Net-(Q2-G)") (class "Default")
      (node (ref "Q2") (pin "1") (pinfunction "G_1") (pintype "unspecified"))
      (node (ref "R8") (pin "2") (pinfunction "2_2") (pintype "input"))
      (node (ref "R9") (pin "2") (pinfunction "2_2") (pintype "input"))
    )
    (net (code "28") (name "Net-(Q3-G)") (class "Default")
      (node (ref "Q3") (pin "1") (pinfunction "G_1") (pintype "input"))
      (node (ref "R10") (pin "2") (pinfunction "2_2") (pintype "input"))
      (node (ref "R6") (pin "1") (pinfunction "1_1") (pintype "input"))
    )
    (net (code "29") (name "Net-(Q4-D)") (class "Default")
      (node (ref "Q4") (pin "3") (pinfunction "D_3") (pintype "unspecified"))
      (node (ref "R17") (pin "1") (pinfunction "1_1") (pintype "input"))
    )
    (net (code "30") (name "Net-(Q4-G)") (class "Default")
      (node (ref "Q4") (pin "1") (pinfunction "G_1") (pintype "unspecified"))
      (node (ref "R19") (pin "2") (pinfunction "2_2") (pintype "input"))
      (node (ref "R21") (pin "2") (pinfunction "2_2") (pintype "input"))
    )
    (net (code "31") (name "Net-(U5-BOOT0)") (class "Default")
      (node (ref "R3") (pin "2") (pinfunction "2_2") (pintype "input"))
      (node (ref "U5") (pin "31") (pinfunction "BOOT0_31") (pintype "unspecified"))
    )
    (net (code "32") (name "Net-(U6-BS)") (class "Default")
      (node (ref "C5") (pin "1") (pinfunction "1_1") (pintype "input"))
      (node (ref "U6") (pin "1") (pinfunction "BS_1") (pintype "input"))
    )
    (net (code "33") (name "Net-(U6-EN)") (class "Default")
      (node (ref "R11") (pin "1") (pinfunction "1_1") (pintype "input"))
      (node (ref "R13") (pin "2") (pinfunction "2_2") (pintype "input"))
      (node (ref "U6") (pin "4") (pinfunction "EN_4") (pintype "input"))
    )
    (net (code "34") (name "Net-(U6-FB)") (class "Default")
      (node (ref "C8") (pin "1") (pinfunction "1_1") (pintype "input"))
      (node (ref "R12") (pin "1") (pinfunction "1_1") (pintype "input"))
      (node (ref "R14") (pin "2") (pinfunction "2_2") (pintype "input"))
      (node (ref "U6") (pin "3") (pinfunction "FB_3") (pintype "input"))
    )
    (net (code "35") (name "Net-(U6-LX)") (class "Default")
      (node (ref "C5") (pin "2") (pinfunction "2_2") (pintype "input"))
      (node (ref "L1") (pin "1") (pinfunction "1_1") (pintype "unspecified"))
      (node (ref "U6") (pin "6") (pinfunction "LX_6") (pintype "input"))
    )
    (net (code "36") (name "PA2") (class "Default")
      (node (ref "R8") (pin "1") (pinfunction "1_1") (pintype "input"))
      (node (ref "U5") (pin "8") (pinfunction "PA2_8") (pintype "unspecified"))
    )
    (net (code "37") (name "VCC") (class "Default")
      (node (ref "C1") (pin "2") (pinfunction "2_2") (pintype "input"))
      (node (ref "C10") (pin "2") (pinfunction "2_2") (pintype "unspecified"))
      (node (ref "C11") (pin "2") (pinfunction "2_2") (pintype "unspecified"))
      (node (ref "C9") (pin "1") (pinfunction "1_1") (pintype "input"))
      (node (ref "Q1") (pin "3") (pinfunction "S_3") (pintype "input"))
      (node (ref "R11") (pin "2") (pinfunction "2_2") (pintype "input"))
      (node (ref "R2") (pin "2") (pinfunction "2_2") (pintype "input"))
      (node (ref "TP1") (pin "1") (pinfunction "1_1") (pintype "input"))
      (node (ref "U1") (pin "1") (pinfunction "1_1") (pintype "unspecified"))
      (node (ref "U6") (pin "5") (pinfunction "IN_5") (pintype "input"))
    )
    (net (code "38") (name "VCCIN-") (class "Default")
      (node (ref "R1") (pin "2") (pinfunction "2_2") (pintype "input"))
      (node (ref "R18") (pin "2") (pinfunction "2_2") (pintype "input"))
      (node (ref "TP3") (pin "1") (pinfunction "1_1") (pintype "input"))
      (node (ref "U3") (pin "5") (pinfunction "IN-_5") (pintype "unspecified"))
      (node (ref "U4") (pin "1") (pinfunction "1_1") (pintype "unspecified"))
    )
    (net (code "39") (name "VDDA") (class "Default")
      (node (ref "R15") (pin "2") (pinfunction "2_2") (pintype "input"))
      (node (ref "U5") (pin "5") (pinfunction "VDDA_5") (pintype "unspecified"))
    )
    (net (code "40") (name "unconnected-(SCREW1-Pad1)") (class "Default")
      (node (ref "SCREW1") (pin "1") (pinfunction "1_1") (pintype "input+no_connect"))
    )
    (net (code "41") (name "unconnected-(SCREW2-Pad1)") (class "Default")
      (node (ref "SCREW2") (pin "1") (pinfunction "1_1") (pintype "input+no_connect"))
    )
    (net (code "42") (name "unconnected-(SCREW3-Pad1)") (class "Default")
      (node (ref "SCREW3") (pin "1") (pinfunction "1_1") (pintype "input+no_connect"))
    )
    (net (code "43") (name "unconnected-(SCREW4-Pad1)") (class "Default")
      (node (ref "SCREW4") (pin "1") (pinfunction "1_1") (pintype "input+no_connect"))
    )
    (net (code "44") (name "unconnected-(SW2-Pad2)") (class "Default")
      (node (ref "SW2") (pin "2") (pinfunction "2_2") (pintype "input+no_connect"))
    )
    (net (code "45") (name "unconnected-(SW2-Pad3)") (class "Default")
      (node (ref "SW2") (pin "3") (pinfunction "3_3") (pintype "input+no_connect"))
    )
    (net (code "46") (name "unconnected-(U5-PA0-Pad6)") (class "Default")
      (node (ref "U5") (pin "6") (pinfunction "PA0_6") (pintype "unspecified+no_connect"))
    )
    (net (code "47") (name "unconnected-(U5-PA1-Pad7)") (class "Default")
      (node (ref "U5") (pin "7") (pinfunction "PA1_7") (pintype "unspecified+no_connect"))
    )
    (net (code "48") (name "unconnected-(U5-PA4-Pad10)") (class "Default")
      (node (ref "U5") (pin "10") (pinfunction "PA4_10") (pintype "unspecified"))
    )
    (net (code "49") (name "unconnected-(U5-PA6-Pad12)") (class "Default")
      (node (ref "U5") (pin "12") (pinfunction "PA6_12") (pintype "unspecified"))
    )
    (net (code "50") (name "unconnected-(U5-PA11-Pad21)") (class "Default")
      (node (ref "U5") (pin "21") (pinfunction "PA11_21") (pintype "unspecified+no_connect"))
    )
    (net (code "51") (name "unconnected-(U5-PA12-Pad22)") (class "Default")
      (node (ref "U5") (pin "22") (pinfunction "PA12_22") (pintype "unspecified+no_connect"))
    )
    (net (code "52") (name "unconnected-(U5-PA15-Pad25)") (class "Default")
      (node (ref "U5") (pin "25") (pinfunction "PA15_25") (pintype "unspecified+no_connect"))
    )
    (net (code "53") (name "unconnected-(U5-PB1-Pad15)") (class "Default")
      (node (ref "U5") (pin "15") (pinfunction "PB1_15") (pintype "unspecified"))
    )
    (net (code "54") (name "unconnected-(U5-PB3-Pad26)") (class "Default")
      (node (ref "U5") (pin "26") (pinfunction "PB3_26") (pintype "unspecified"))
    )
    (net (code "55") (name "unconnected-(U5-PB4-Pad27)") (class "Default")
      (node (ref "U5") (pin "27") (pinfunction "PB4_27") (pintype "unspecified+no_connect"))
    )
    (net (code "56") (name "unconnected-(U5-PB5-Pad28)") (class "Default")
      (node (ref "U5") (pin "28") (pinfunction "PB5_28") (pintype "unspecified"))
    )
    (net (code "57") (name "unconnected-(U5-PB6-Pad29)") (class "Default")
      (node (ref "U5") (pin "29") (pinfunction "PB6_29") (pintype "unspecified+no_connect"))
    )
    (net (code "58") (name "unconnected-(U5-PB7-Pad30)") (class "Default")
      (node (ref "U5") (pin "30") (pinfunction "PB7_30") (pintype "unspecified+no_connect"))
    )
    (net (code "59") (name "unconnected-(U5-PB8-Pad32)") (class "Default")
      (node (ref "U5") (pin "32") (pinfunction "PB8_32") (pintype "unspecified+no_connect"))
    )
    (net (code "60") (name "unconnected-(U8-NC-Pad1)") (class "Default")
      (node (ref "U8") (pin "1") (pinfunction "NC_1") (pintype "unspecified+no_connect"))
    )
    (net (code "61") (name "unconnected-(U8-NC-Pad2)") (class "Default")
      (node (ref "U8") (pin "2") (pinfunction "NC_2") (pintype "unspecified+no_connect"))
    )
    (net (code "62") (name "unconnected-(U8-NC-Pad9)") (class "Default")
      (node (ref "U8") (pin "9") (pinfunction "NC_9") (pintype "unspecified+no_connect"))
    )
  )
)
